# weight_sens.net
KiCad netlist of a schematic drawn in EAGLE
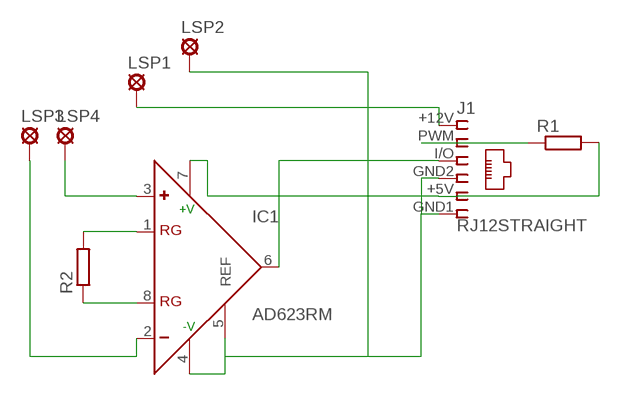
[diagram p0: schematic, sheet 1]

(export (version "E")
  (design (tool "Eeschema 10.0.6"))
  (components
    (comp (ref "IC1")
      (value "AD623RM")
      (footprint "eagle-import:MSOP08")
      (fields (field (name "MPN") "AD623ARMZ"))
      (libsource (lib "eagle-import") (part "AD623RM"))
    )
    (comp (ref "J1")
      (value "RJ12STRAIGHT")
      (footprint "eagle-import:RJ12-STRAIGHT")
      (libsource (lib "eagle-import") (part "RJ12STRAIGHT"))
    )
    (comp (ref "LSP1")
      (value "LSP10")
      (footprint "eagle-import:LSP10")
      (libsource (lib "eagle-import") (part "LSP10"))
    )
    (comp (ref "LSP2")
      (value "LSP10")
      (footprint "eagle-import:LSP10")
      (libsource (lib "eagle-import") (part "LSP10"))
    )
    (comp (ref "LSP3")
      (value "LSP10")
      (footprint "eagle-import:LSP10")
      (libsource (lib "eagle-import") (part "LSP10"))
    )
    (comp (ref "LSP4")
      (value "LSP10")
      (footprint "eagle-import:LSP10")
      (libsource (lib "eagle-import") (part "LSP10"))
    )
    (comp (ref "R1")
      (value "R-EU_M1206")
      (footprint "eagle-import:M1206")
      (libsource (lib "eagle-import") (part "R-EU_M1206"))
    )
    (comp (ref "R2")
      (value "R-EU_R1206")
      (footprint "eagle-import:R1206")
      (libsource (lib "eagle-import") (part "resistor_R-EU_R1206"))
    )
  )
  (nets
    (net (code "1") (name "Net-(IC1-+)") (class "Default")
      (node (ref "IC1") (pin "3") (pinfunction "+_3") (pintype "input"))
      (node (ref "LSP4") (pin "MP") (pinfunction "MP_MP") (pintype "passive"))
    )
    (net (code "2") (name "Net-(IC1-+V)") (class "Default")
      (node (ref "IC1") (pin "7") (pinfunction "+V_7") (pintype "power_in"))
      (node (ref "J1") (pin "+5V") (pinfunction "5_+5V") (pintype "bidirectional"))
      (node (ref "R1") (pin "2") (pinfunction "2_2") (pintype "passive"))
    )
    (net (code "3") (name "Net-(IC1--)") (class "Default")
      (node (ref "IC1") (pin "2") (pinfunction "-_2") (pintype "input"))
      (node (ref "LSP3") (pin "MP") (pinfunction "MP_MP") (pintype "passive"))
    )
    (net (code "4") (name "Net-(IC1--V)") (class "Default")
      (node (ref "IC1") (pin "4") (pinfunction "-V_4") (pintype "power_in"))
      (node (ref "IC1") (pin "5") (pinfunction "REF_5") (pintype "passive"))
      (node (ref "J1") (pin "GND1") (pinfunction "6_GND1") (pintype "bidirectional"))
      (node (ref "J1") (pin "GND2") (pinfunction "4_GND2") (pintype "bidirectional"))
      (node (ref "LSP2") (pin "MP") (pinfunction "MP_MP") (pintype "passive"))
    )
    (net (code "5") (name "Net-(IC1-OUT)") (class "Default")
      (node (ref "IC1") (pin "6") (pinfunction "OUT_6") (pintype "output"))
      (node (ref "J1") (pin "I/O") (pinfunction "3_I/O") (pintype "bidirectional"))
    )
    (net (code "6") (name "Net-(IC1-RG-Pad1)") (class "Default")
      (node (ref "IC1") (pin "1") (pinfunction "RG_1") (pintype "passive"))
      (node (ref "R2") (pin "2") (pinfunction "2_2") (pintype "passive"))
    )
    (net (code "7") (name "Net-(IC1-RG-Pad8)") (class "Default")
      (node (ref "IC1") (pin "8") (pinfunction "RG_8") (pintype "passive"))
      (node (ref "R2") (pin "1") (pinfunction "1_1") (pintype "passive"))
    )
    (net (code "8") (name "Net-(J1-1)") (class "Default")
      (node (ref "J1") (pin "+12V") (pinfunction "1_+12V") (pintype "bidirectional"))
      (node (ref "LSP1") (pin "MP") (pinfunction "MP_MP") (pintype "passive"))
    )
    (net (code "9") (name "Net-(J1-2)") (class "Default")
      (node (ref "J1") (pin "PWM") (pinfunction "2_PWM") (pintype "bidirectional"))
      (node (ref "R1") (pin "1") (pinfunction "1_1") (pintype "passive"))
    )
  )
)
